# ASD2421.net
KiCad netlist of a schematic drawn in EAGLE
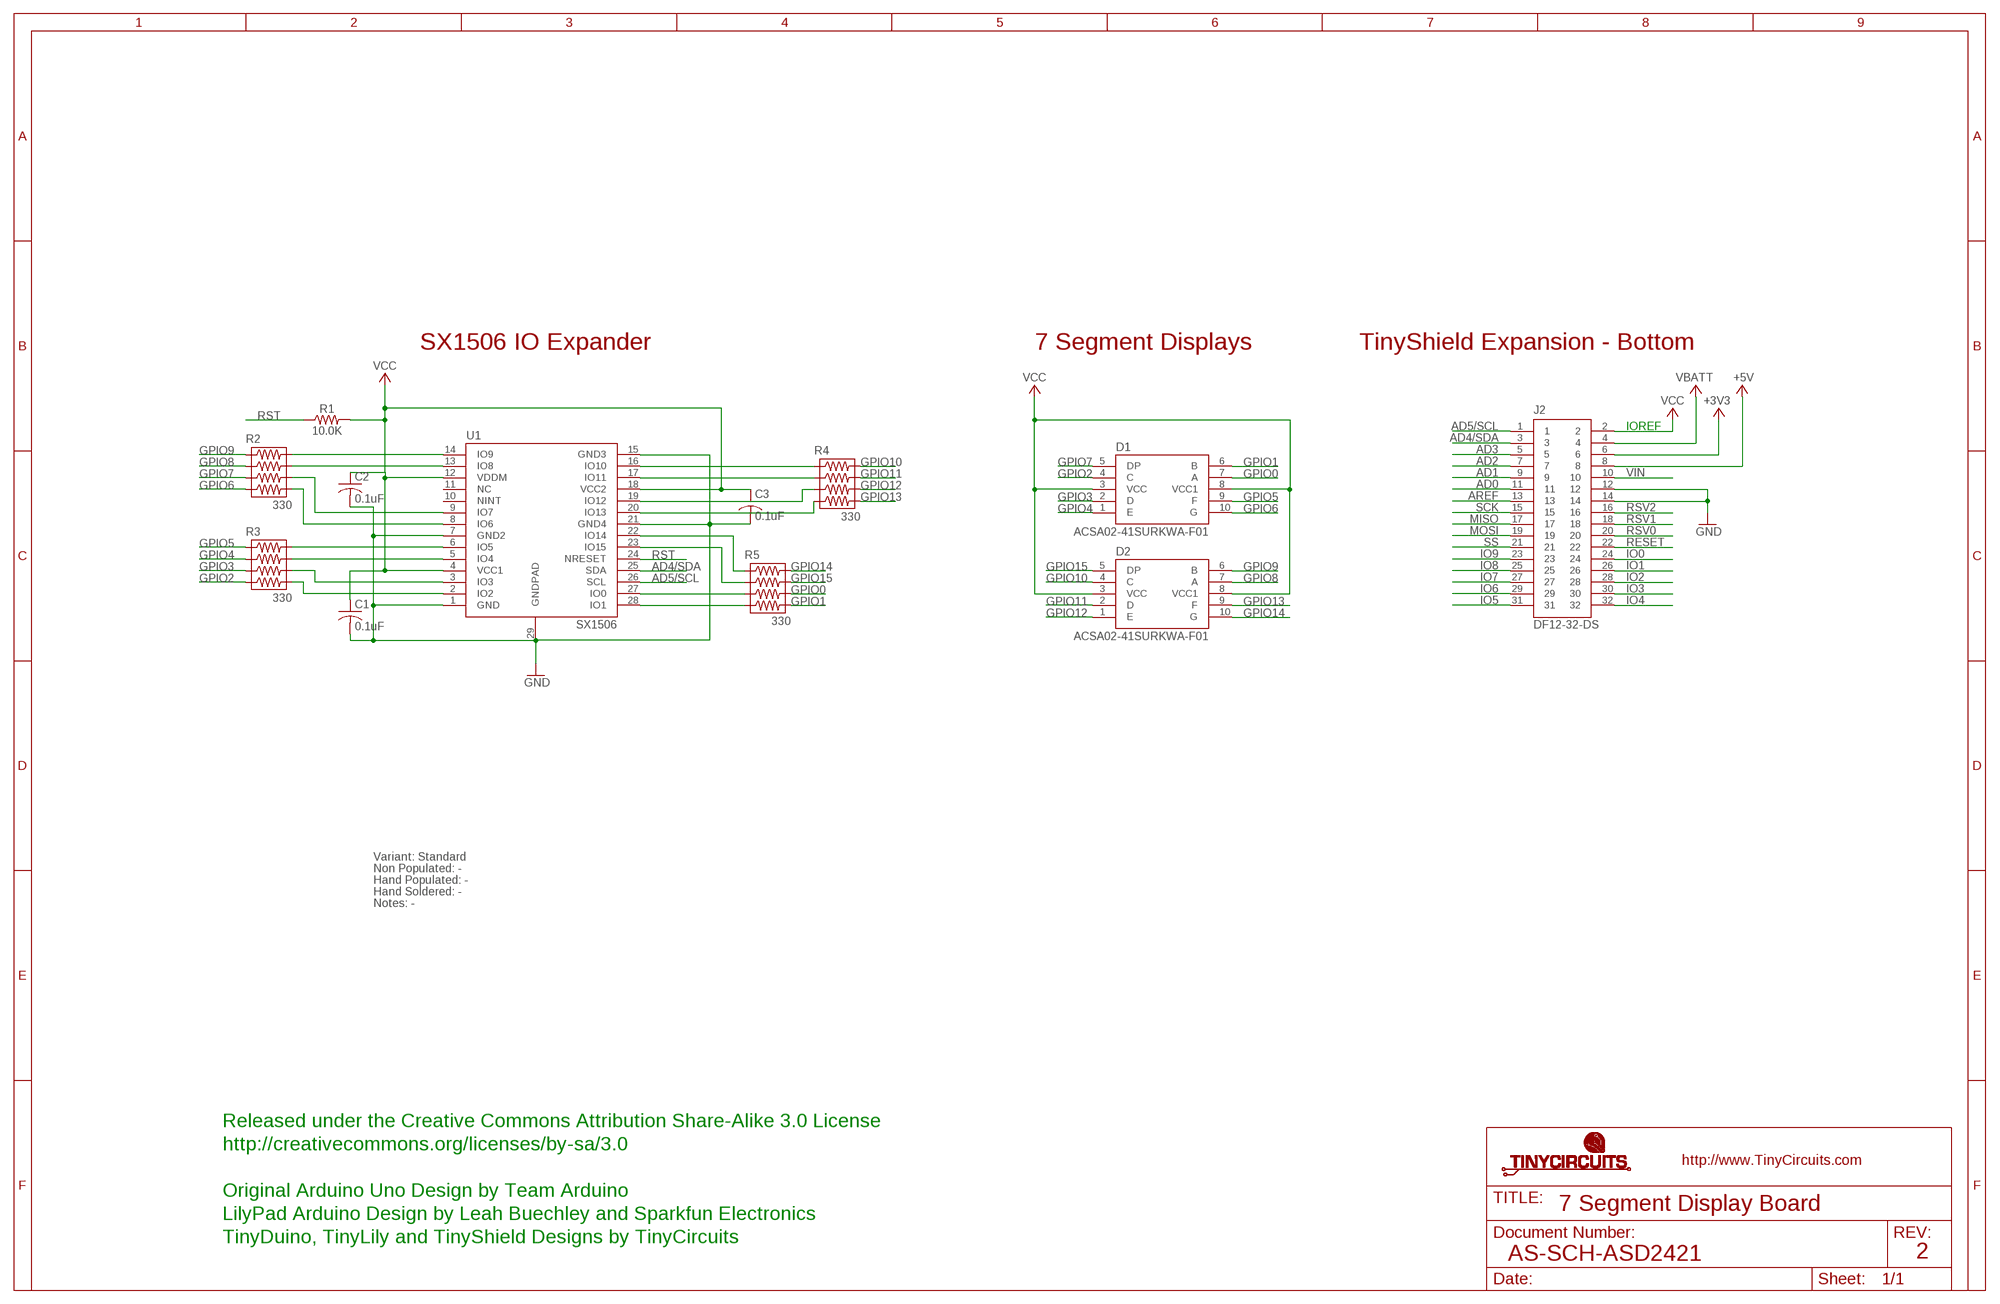
[diagram p0: schematic, sheet 1]

(export (version "E")
  (design (tool "Eeschema 10.0.6"))
  (components
    (comp (ref "C1")
      (value "0.1uF")
      (footprint "eagle-import:C0402")
      (fields (field (name "PARTNO") "AS-ITM-00008"))
      (libsource (lib "eagle-import") (part "AS-ITM-00008"))
    )
    (comp (ref "C2")
      (value "0.1uF")
      (footprint "eagle-import:C0402")
      (fields (field (name "PARTNO") "AS-ITM-00008"))
      (libsource (lib "eagle-import") (part "AS-ITM-00008"))
    )
    (comp (ref "C3")
      (value "0.1uF")
      (footprint "eagle-import:C0402")
      (fields (field (name "PARTNO") "AS-ITM-00008"))
      (libsource (lib "eagle-import") (part "AS-ITM-00008"))
    )
    (comp (ref "D1")
      (value "ACSA02-41SURKWA-F01")
      (footprint "eagle-import:ACSA02-41SURKWA-F01")
      (fields (field (name "PARTNO") "AS-ITM-00133") (field (name "PARTNO_1") "AS-ITM-00133"))
      (libsource (lib "eagle-import") (part "AS-ITM-00133"))
    )
    (comp (ref "D2")
      (value "ACSA02-41SURKWA-F01")
      (footprint "eagle-import:ACSA02-41SURKWA-F01")
      (fields (field (name "PARTNO") "AS-ITM-00133") (field (name "PARTNO_1") "AS-ITM-00133"))
      (libsource (lib "eagle-import") (part "AS-ITM-00133"))
    )
    (comp (ref "J2")
      (value "DF12-32-DS")
      (footprint "eagle-import:DF12-32-DS")
      (fields (field (name "PARTNO") "AS-ITM-00012") (field (name "PARTNO_1") "AS-ITM-00012"))
      (libsource (lib "eagle-import") (part "AS-ITM-00012"))
    )
    (comp (ref "R1")
      (value "10.0K")
      (footprint "eagle-import:0402")
      (fields (field (name "PARTNO") "AS-ITM-00032"))
      (libsource (lib "eagle-import") (part "AS-ITM-00032"))
    )
    (comp (ref "R2")
      (value "330")
      (footprint "eagle-import:0402RPACK")
      (fields (field (name "PARTNO") "AS-ITM-00135"))
      (libsource (lib "eagle-import") (part "AS-ITM-00135"))
    )
    (comp (ref "R3")
      (value "330")
      (footprint "eagle-import:0402RPACK")
      (fields (field (name "PARTNO") "AS-ITM-00135"))
      (libsource (lib "eagle-import") (part "AS-ITM-00135"))
    )
    (comp (ref "R4")
      (value "330")
      (footprint "eagle-import:0402RPACK")
      (fields (field (name "PARTNO") "AS-ITM-00135"))
      (libsource (lib "eagle-import") (part "AS-ITM-00135"))
    )
    (comp (ref "R5")
      (value "330")
      (footprint "eagle-import:0402RPACK")
      (fields (field (name "PARTNO") "AS-ITM-00135"))
      (libsource (lib "eagle-import") (part "AS-ITM-00135"))
    )
    (comp (ref "U1")
      (value "SX1506")
      (footprint "eagle-import:SX1506")
      (fields (field (name "PARTNO") "AS-ITM-00134") (field (name "PARTNO_1") "AS-ITM-00134"))
      (libsource (lib "eagle-import") (part "AS-ITM-00134"))
    )
  )
  (nets
    (net (code "1") (name "+3V3") (class "Default")
      (node (ref "J2") (pin "6") (pinfunction "6_6") (pintype "bidirectional"))
    )
    (net (code "2") (name "+5V") (class "Default")
      (node (ref "J2") (pin "8") (pinfunction "8_8") (pintype "bidirectional"))
    )
    (net (code "3") (name "/AD0") (class "Default")
      (node (ref "J2") (pin "11") (pinfunction "11_11") (pintype "bidirectional"))
    )
    (net (code "4") (name "/AD1") (class "Default")
      (node (ref "J2") (pin "9") (pinfunction "9_9") (pintype "bidirectional"))
    )
    (net (code "5") (name "/AD2") (class "Default")
      (node (ref "J2") (pin "7") (pinfunction "7_7") (pintype "bidirectional"))
    )
    (net (code "6") (name "/AD3") (class "Default")
      (node (ref "J2") (pin "5") (pinfunction "5_5") (pintype "bidirectional"))
    )
    (net (code "7") (name "/AD4{slash}SDA") (class "Default")
      (node (ref "J2") (pin "3") (pinfunction "3_3") (pintype "bidirectional"))
      (node (ref "U1") (pin "25") (pinfunction "SDA_25") (pintype "bidirectional"))
    )
    (net (code "8") (name "/AD5{slash}SCL") (class "Default")
      (node (ref "J2") (pin "1") (pinfunction "1_1") (pintype "bidirectional"))
      (node (ref "U1") (pin "26") (pinfunction "SCL_26") (pintype "bidirectional"))
    )
    (net (code "9") (name "/AREF") (class "Default")
      (node (ref "J2") (pin "13") (pinfunction "13_13") (pintype "bidirectional"))
    )
    (net (code "10") (name "/GPIO0") (class "Default")
      (node (ref "D1") (pin "7") (pinfunction "A_7") (pintype "bidirectional"))
      (node (ref "R5") (pin "6") (pinfunction "6_6") (pintype "passive"))
    )
    (net (code "11") (name "/GPIO1") (class "Default")
      (node (ref "D1") (pin "6") (pinfunction "B_6") (pintype "bidirectional"))
      (node (ref "R5") (pin "8") (pinfunction "8_8") (pintype "passive"))
    )
    (net (code "12") (name "/GPIO2") (class "Default")
      (node (ref "D1") (pin "4") (pinfunction "C_4") (pintype "bidirectional"))
      (node (ref "R3") (pin "7") (pinfunction "7_7") (pintype "passive"))
    )
    (net (code "13") (name "/GPIO3") (class "Default")
      (node (ref "D1") (pin "2") (pinfunction "D_2") (pintype "bidirectional"))
      (node (ref "R3") (pin "5") (pinfunction "5_5") (pintype "passive"))
    )
    (net (code "14") (name "/GPIO4") (class "Default")
      (node (ref "D1") (pin "1") (pinfunction "E_1") (pintype "bidirectional"))
      (node (ref "R3") (pin "3") (pinfunction "3_3") (pintype "passive"))
    )
    (net (code "15") (name "/GPIO5") (class "Default")
      (node (ref "D1") (pin "9") (pinfunction "F_9") (pintype "bidirectional"))
      (node (ref "R3") (pin "1") (pinfunction "1_1") (pintype "passive"))
    )
    (net (code "16") (name "/GPIO6") (class "Default")
      (node (ref "D1") (pin "10") (pinfunction "G_10") (pintype "bidirectional"))
      (node (ref "R2") (pin "7") (pinfunction "7_7") (pintype "passive"))
    )
    (net (code "17") (name "/GPIO7") (class "Default")
      (node (ref "D1") (pin "5") (pinfunction "DP_5") (pintype "bidirectional"))
      (node (ref "R2") (pin "5") (pinfunction "5_5") (pintype "passive"))
    )
    (net (code "18") (name "/GPIO8") (class "Default")
      (node (ref "D2") (pin "7") (pinfunction "A_7") (pintype "bidirectional"))
      (node (ref "R2") (pin "3") (pinfunction "3_3") (pintype "passive"))
    )
    (net (code "19") (name "/GPIO9") (class "Default")
      (node (ref "D2") (pin "6") (pinfunction "B_6") (pintype "bidirectional"))
      (node (ref "R2") (pin "1") (pinfunction "1_1") (pintype "passive"))
    )
    (net (code "20") (name "/GPIO10") (class "Default")
      (node (ref "D2") (pin "4") (pinfunction "C_4") (pintype "bidirectional"))
      (node (ref "R4") (pin "2") (pinfunction "2_2") (pintype "passive"))
    )
    (net (code "21") (name "/GPIO11") (class "Default")
      (node (ref "D2") (pin "2") (pinfunction "D_2") (pintype "bidirectional"))
      (node (ref "R4") (pin "4") (pinfunction "4_4") (pintype "passive"))
    )
    (net (code "22") (name "/GPIO12") (class "Default")
      (node (ref "D2") (pin "1") (pinfunction "E_1") (pintype "bidirectional"))
      (node (ref "R4") (pin "6") (pinfunction "6_6") (pintype "passive"))
    )
    (net (code "23") (name "/GPIO13") (class "Default")
      (node (ref "D2") (pin "9") (pinfunction "F_9") (pintype "bidirectional"))
      (node (ref "R4") (pin "8") (pinfunction "8_8") (pintype "passive"))
    )
    (net (code "24") (name "/GPIO14") (class "Default")
      (node (ref "D2") (pin "10") (pinfunction "G_10") (pintype "bidirectional"))
      (node (ref "R5") (pin "2") (pinfunction "2_2") (pintype "passive"))
    )
    (net (code "25") (name "/GPIO15") (class "Default")
      (node (ref "D2") (pin "5") (pinfunction "DP_5") (pintype "bidirectional"))
      (node (ref "R5") (pin "4") (pinfunction "4_4") (pintype "passive"))
    )
    (net (code "26") (name "/IO0") (class "Default")
      (node (ref "J2") (pin "24") (pinfunction "24_24") (pintype "bidirectional"))
    )
    (net (code "27") (name "/IO1") (class "Default")
      (node (ref "J2") (pin "26") (pinfunction "26_26") (pintype "bidirectional"))
    )
    (net (code "28") (name "/IO2") (class "Default")
      (node (ref "J2") (pin "28") (pinfunction "28_28") (pintype "bidirectional"))
    )
    (net (code "29") (name "/IO3") (class "Default")
      (node (ref "J2") (pin "30") (pinfunction "30_30") (pintype "bidirectional"))
    )
    (net (code "30") (name "/IO4") (class "Default")
      (node (ref "J2") (pin "32") (pinfunction "32_32") (pintype "bidirectional"))
    )
    (net (code "31") (name "/IO5") (class "Default")
      (node (ref "J2") (pin "31") (pinfunction "31_31") (pintype "bidirectional"))
    )
    (net (code "32") (name "/IO6") (class "Default")
      (node (ref "J2") (pin "29") (pinfunction "29_29") (pintype "bidirectional"))
    )
    (net (code "33") (name "/IO7") (class "Default")
      (node (ref "J2") (pin "27") (pinfunction "27_27") (pintype "bidirectional"))
    )
    (net (code "34") (name "/IO8") (class "Default")
      (node (ref "J2") (pin "25") (pinfunction "25_25") (pintype "bidirectional"))
    )
    (net (code "35") (name "/IO9") (class "Default")
      (node (ref "J2") (pin "23") (pinfunction "23_23") (pintype "bidirectional"))
    )
    (net (code "36") (name "/MISO") (class "Default")
      (node (ref "J2") (pin "17") (pinfunction "17_17") (pintype "bidirectional"))
    )
    (net (code "37") (name "/MOSI") (class "Default")
      (node (ref "J2") (pin "19") (pinfunction "19_19") (pintype "bidirectional"))
    )
    (net (code "38") (name "/RESET") (class "Default")
      (node (ref "J2") (pin "22") (pinfunction "22_22") (pintype "bidirectional"))
    )
    (net (code "39") (name "/RST") (class "Default")
      (node (ref "R1") (pin "1") (pinfunction "1_1") (pintype "passive"))
      (node (ref "U1") (pin "24") (pinfunction "NRESET_24") (pintype "bidirectional"))
    )
    (net (code "40") (name "/RSV0") (class "Default")
      (node (ref "J2") (pin "20") (pinfunction "20_20") (pintype "bidirectional"))
    )
    (net (code "41") (name "/RSV1") (class "Default")
      (node (ref "J2") (pin "18") (pinfunction "18_18") (pintype "bidirectional"))
    )
    (net (code "42") (name "/RSV2") (class "Default")
      (node (ref "J2") (pin "16") (pinfunction "16_16") (pintype "bidirectional"))
    )
    (net (code "43") (name "/SCK") (class "Default")
      (node (ref "J2") (pin "15") (pinfunction "15_15") (pintype "bidirectional"))
    )
    (net (code "44") (name "/SS") (class "Default")
      (node (ref "J2") (pin "21") (pinfunction "21_21") (pintype "bidirectional"))
    )
    (net (code "45") (name "/VIN") (class "Default")
      (node (ref "J2") (pin "10") (pinfunction "10_10") (pintype "bidirectional"))
    )
    (net (code "46") (name "GND") (class "Default")
      (node (ref "C1") (pin "2") (pinfunction "2_2") (pintype "passive"))
      (node (ref "C2") (pin "2") (pinfunction "2_2") (pintype "passive"))
      (node (ref "C3") (pin "2") (pinfunction "2_2") (pintype "passive"))
      (node (ref "J2") (pin "12") (pinfunction "12_12") (pintype "bidirectional"))
      (node (ref "J2") (pin "14") (pinfunction "14_14") (pintype "bidirectional"))
      (node (ref "U1") (pin "1") (pinfunction "GND_1") (pintype "bidirectional"))
      (node (ref "U1") (pin "15") (pinfunction "GND3_15") (pintype "bidirectional"))
      (node (ref "U1") (pin "21") (pinfunction "GND4_21") (pintype "bidirectional"))
      (node (ref "U1") (pin "29") (pinfunction "GNDPAD_29") (pintype "bidirectional"))
      (node (ref "U1") (pin "7") (pinfunction "GND2_7") (pintype "bidirectional"))
    )
    (net (code "47") (name "Net-(U1-IO0)") (class "Default")
      (node (ref "R5") (pin "5") (pinfunction "5_5") (pintype "passive"))
      (node (ref "U1") (pin "27") (pinfunction "IO0_27") (pintype "bidirectional"))
    )
    (net (code "48") (name "Net-(U1-IO1)") (class "Default")
      (node (ref "R5") (pin "7") (pinfunction "7_7") (pintype "passive"))
      (node (ref "U1") (pin "28") (pinfunction "IO1_28") (pintype "bidirectional"))
    )
    (net (code "49") (name "Net-(U1-IO2)") (class "Default")
      (node (ref "R3") (pin "8") (pinfunction "8_8") (pintype "passive"))
      (node (ref "U1") (pin "2") (pinfunction "IO2_2") (pintype "bidirectional"))
    )
    (net (code "50") (name "Net-(U1-IO3)") (class "Default")
      (node (ref "R3") (pin "6") (pinfunction "6_6") (pintype "passive"))
      (node (ref "U1") (pin "3") (pinfunction "IO3_3") (pintype "bidirectional"))
    )
    (net (code "51") (name "Net-(U1-IO4)") (class "Default")
      (node (ref "R3") (pin "4") (pinfunction "4_4") (pintype "passive"))
      (node (ref "U1") (pin "5") (pinfunction "IO4_5") (pintype "bidirectional"))
    )
    (net (code "52") (name "Net-(U1-IO5)") (class "Default")
      (node (ref "R3") (pin "2") (pinfunction "2_2") (pintype "passive"))
      (node (ref "U1") (pin "6") (pinfunction "IO5_6") (pintype "bidirectional"))
    )
    (net (code "53") (name "Net-(U1-IO6)") (class "Default")
      (node (ref "R2") (pin "8") (pinfunction "8_8") (pintype "passive"))
      (node (ref "U1") (pin "8") (pinfunction "IO6_8") (pintype "bidirectional"))
    )
    (net (code "54") (name "Net-(U1-IO7)") (class "Default")
      (node (ref "R2") (pin "6") (pinfunction "6_6") (pintype "passive"))
      (node (ref "U1") (pin "9") (pinfunction "IO7_9") (pintype "bidirectional"))
    )
    (net (code "55") (name "Net-(U1-IO8)") (class "Default")
      (node (ref "R2") (pin "4") (pinfunction "4_4") (pintype "passive"))
      (node (ref "U1") (pin "13") (pinfunction "IO8_13") (pintype "bidirectional"))
    )
    (net (code "56") (name "Net-(U1-IO9)") (class "Default")
      (node (ref "R2") (pin "2") (pinfunction "2_2") (pintype "passive"))
      (node (ref "U1") (pin "14") (pinfunction "IO9_14") (pintype "bidirectional"))
    )
    (net (code "57") (name "Net-(U1-IO10)") (class "Default")
      (node (ref "R4") (pin "1") (pinfunction "1_1") (pintype "passive"))
      (node (ref "U1") (pin "16") (pinfunction "IO10_16") (pintype "bidirectional"))
    )
    (net (code "58") (name "Net-(U1-IO11)") (class "Default")
      (node (ref "R4") (pin "3") (pinfunction "3_3") (pintype "passive"))
      (node (ref "U1") (pin "17") (pinfunction "IO11_17") (pintype "bidirectional"))
    )
    (net (code "59") (name "Net-(U1-IO12)") (class "Default")
      (node (ref "R4") (pin "5") (pinfunction "5_5") (pintype "passive"))
      (node (ref "U1") (pin "19") (pinfunction "IO12_19") (pintype "bidirectional"))
    )
    (net (code "60") (name "Net-(U1-IO13)") (class "Default")
      (node (ref "R4") (pin "7") (pinfunction "7_7") (pintype "passive"))
      (node (ref "U1") (pin "20") (pinfunction "IO13_20") (pintype "bidirectional"))
    )
    (net (code "61") (name "Net-(U1-IO14)") (class "Default")
      (node (ref "R5") (pin "1") (pinfunction "1_1") (pintype "passive"))
      (node (ref "U1") (pin "22") (pinfunction "IO14_22") (pintype "bidirectional"))
    )
    (net (code "62") (name "Net-(U1-IO15)") (class "Default")
      (node (ref "R5") (pin "3") (pinfunction "3_3") (pintype "passive"))
      (node (ref "U1") (pin "23") (pinfunction "IO15_23") (pintype "bidirectional"))
    )
    (net (code "63") (name "VBATT") (class "Default")
      (node (ref "J2") (pin "4") (pinfunction "4_4") (pintype "bidirectional"))
    )
    (net (code "64") (name "VCC") (class "Default")
      (node (ref "C1") (pin "1") (pinfunction "1_1") (pintype "passive"))
      (node (ref "C2") (pin "1") (pinfunction "1_1") (pintype "passive"))
      (node (ref "C3") (pin "1") (pinfunction "1_1") (pintype "passive"))
      (node (ref "D1") (pin "3") (pinfunction "VCC_3") (pintype "bidirectional"))
      (node (ref "D1") (pin "8") (pinfunction "VCC1_8") (pintype "bidirectional"))
      (node (ref "D2") (pin "3") (pinfunction "VCC_3") (pintype "bidirectional"))
      (node (ref "D2") (pin "8") (pinfunction "VCC1_8") (pintype "bidirectional"))
      (node (ref "J2") (pin "2") (pinfunction "2_2") (pintype "bidirectional"))
      (node (ref "R1") (pin "2") (pinfunction "2_2") (pintype "passive"))
      (node (ref "U1") (pin "12") (pinfunction "VDDM_12") (pintype "bidirectional"))
      (node (ref "U1") (pin "18") (pinfunction "VCC2_18") (pintype "bidirectional"))
      (node (ref "U1") (pin "4") (pinfunction "VCC1_4") (pintype "bidirectional"))
    )
    (net (code "65") (name "unconnected-(U1-NC-Pad11)") (class "Default")
      (node (ref "U1") (pin "11") (pinfunction "NC_11") (pintype "bidirectional"))
    )
    (net (code "66") (name "unconnected-(U1-NINT-Pad10)") (class "Default")
      (node (ref "U1") (pin "10") (pinfunction "NINT_10") (pintype "bidirectional"))
    )
  )
)
